# 2_waffling60-BK_matrix.net
KiCad netlist of a schematic drawn in Altium Designer
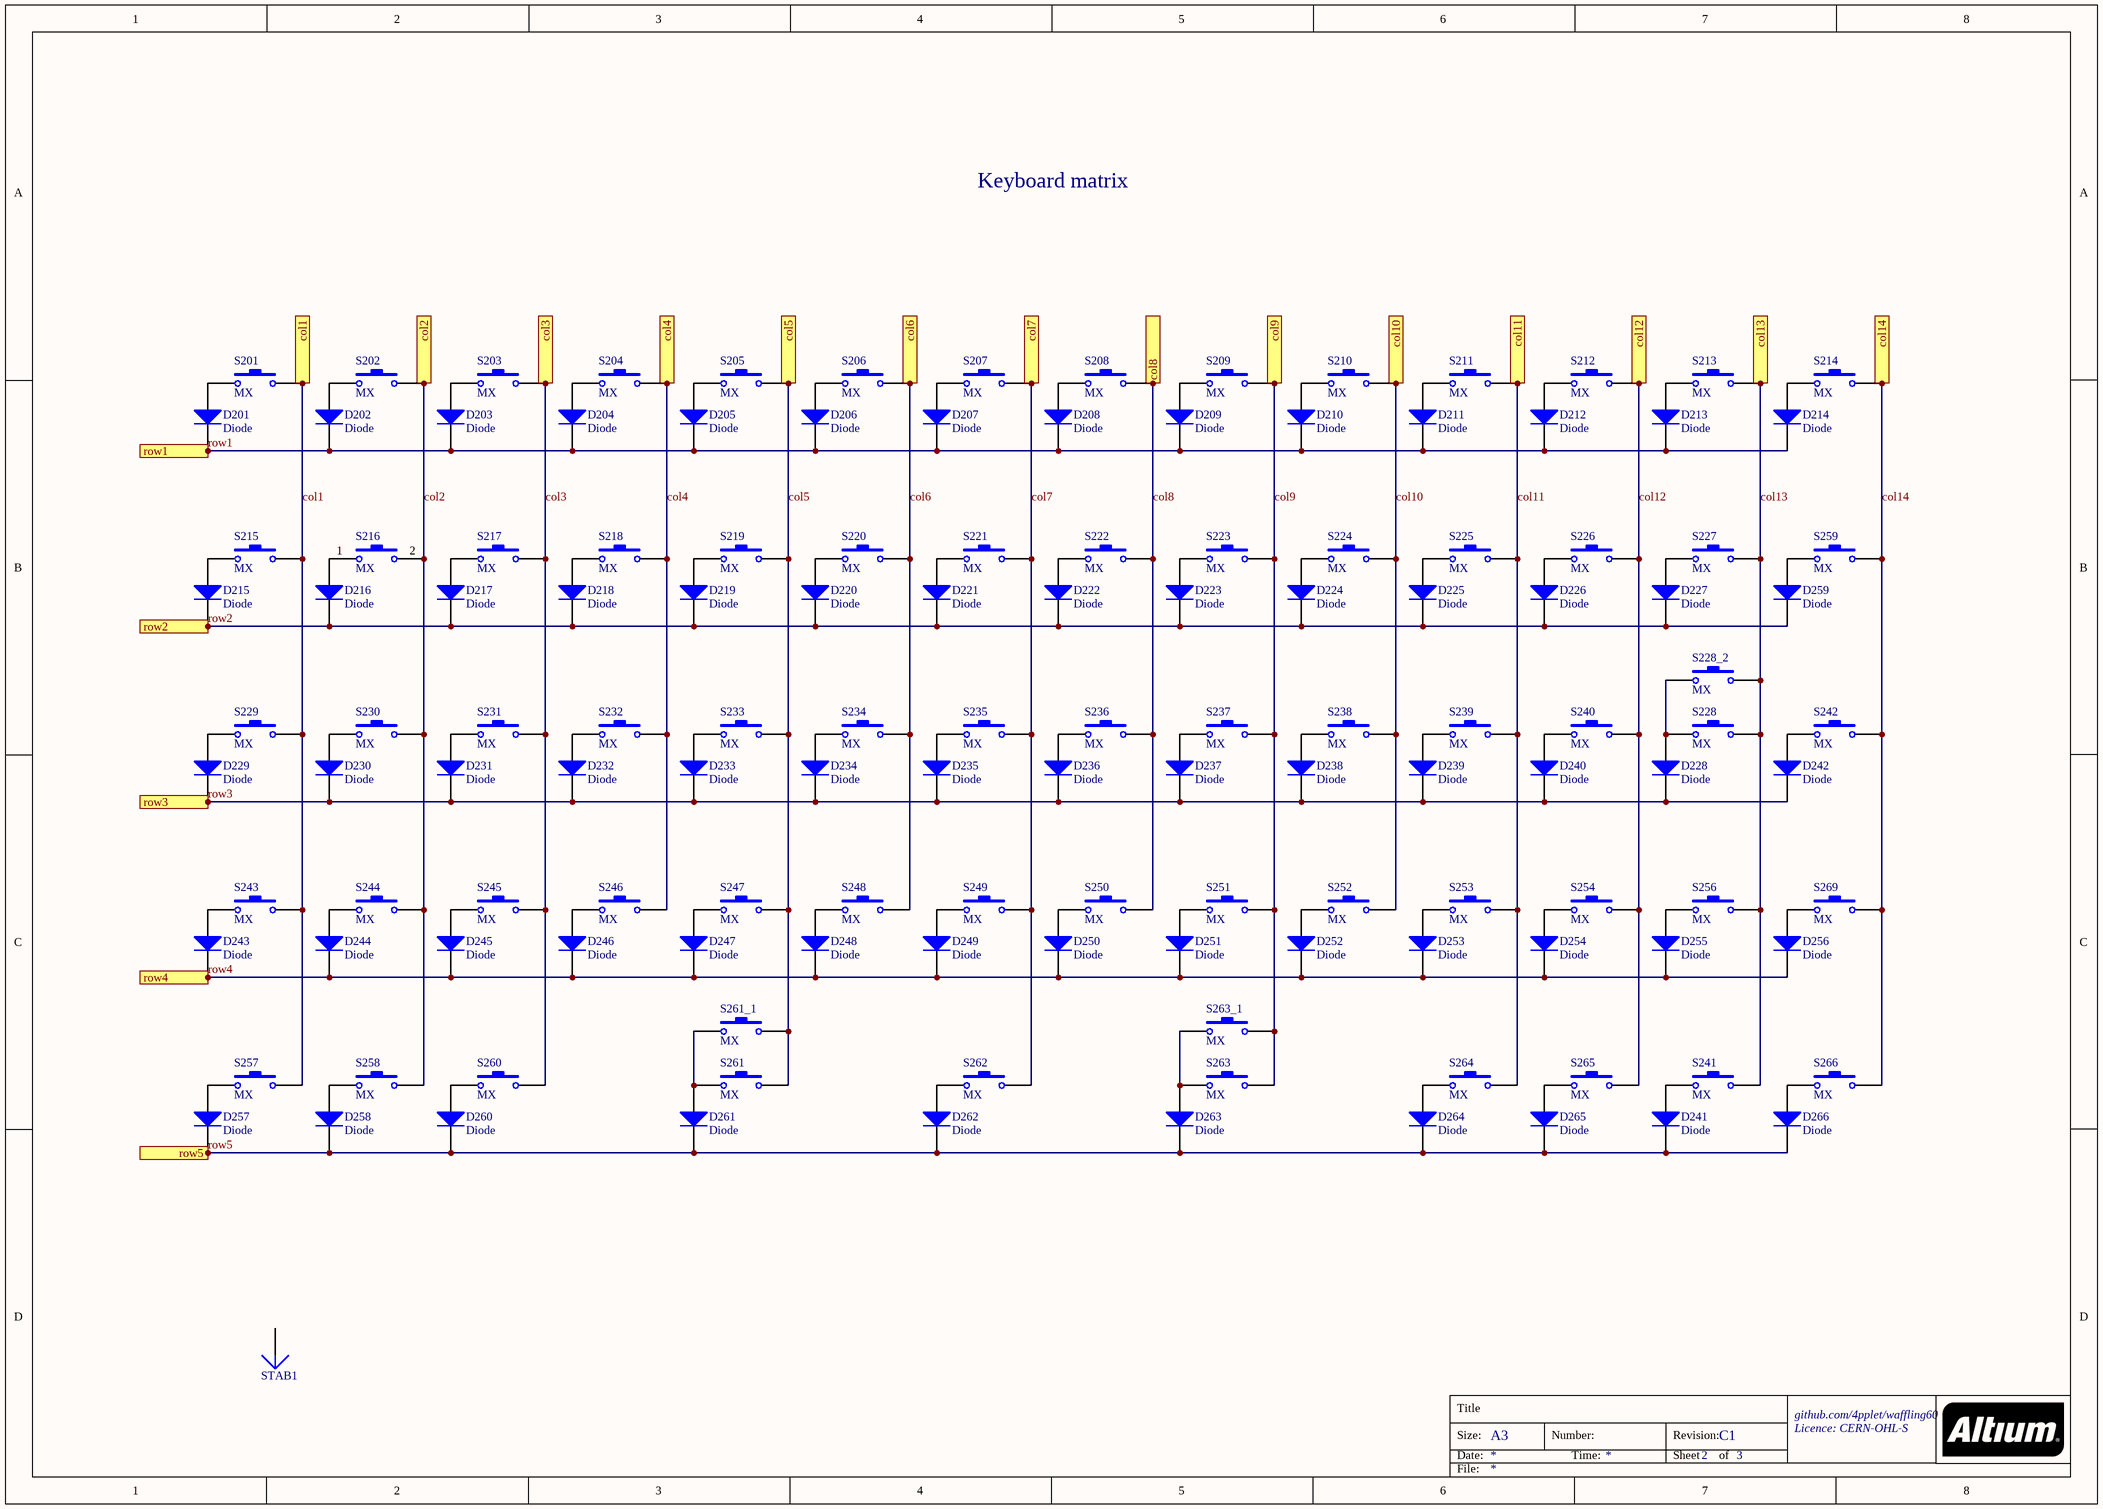
[diagram p0: 2_waffling60-BK_matrix.SchDoc]

(export (version "E")
  (design (tool "Eeschema 10.0.6"))
  (components
    (comp (ref "D201")
      (value "Diode")
      (footprint "SOD-123")
      (description "Default Diode")
      (fields (field (name "LCSC PART #") "C81598") (field (name "MRF.PART") "1N4148W"))
      (libsource (lib "Miscellaneous Devices") (part "Diode"))
    )
    (comp (ref "D202")
      (value "Diode")
      (footprint "SOD-123")
      (description "Default Diode")
      (fields (field (name "LCSC PART #") "C81598") (field (name "MRF.PART") "1N4148W"))
      (libsource (lib "Miscellaneous Devices") (part "Diode"))
    )
    (comp (ref "D203")
      (value "Diode")
      (footprint "SOD-123")
      (description "Default Diode")
      (fields (field (name "LCSC PART #") "C81598") (field (name "MRF.PART") "1N4148W"))
      (libsource (lib "Miscellaneous Devices") (part "Diode"))
    )
    (comp (ref "D204")
      (value "Diode")
      (footprint "SOD-123")
      (description "Default Diode")
      (fields (field (name "LCSC PART #") "C81598") (field (name "MRF.PART") "1N4148W"))
      (libsource (lib "Miscellaneous Devices") (part "Diode"))
    )
    (comp (ref "D205")
      (value "Diode")
      (footprint "SOD-123")
      (description "Default Diode")
      (fields (field (name "LCSC PART #") "C81598") (field (name "MRF.PART") "1N4148W"))
      (libsource (lib "Miscellaneous Devices") (part "Diode"))
    )
    (comp (ref "D206")
      (value "Diode")
      (footprint "SOD-123")
      (description "Default Diode")
      (fields (field (name "LCSC PART #") "C81598") (field (name "MRF.PART") "1N4148W"))
      (libsource (lib "Miscellaneous Devices") (part "Diode"))
    )
    (comp (ref "D207")
      (value "Diode")
      (footprint "SOD-123")
      (description "Default Diode")
      (fields (field (name "LCSC PART #") "C81598") (field (name "MRF.PART") "1N4148W"))
      (libsource (lib "Miscellaneous Devices") (part "Diode"))
    )
    (comp (ref "D208")
      (value "Diode")
      (footprint "SOD-123")
      (description "Default Diode")
      (fields (field (name "LCSC PART #") "C81598") (field (name "MRF.PART") "1N4148W"))
      (libsource (lib "Miscellaneous Devices") (part "Diode"))
    )
    (comp (ref "D209")
      (value "Diode")
      (footprint "SOD-123")
      (description "Default Diode")
      (fields (field (name "LCSC PART #") "C81598") (field (name "MRF.PART") "1N4148W"))
      (libsource (lib "Miscellaneous Devices") (part "Diode"))
    )
    (comp (ref "D210")
      (value "Diode")
      (footprint "SOD-123")
      (description "Default Diode")
      (fields (field (name "LCSC PART #") "C81598") (field (name "MRF.PART") "1N4148W"))
      (libsource (lib "Miscellaneous Devices") (part "Diode"))
    )
    (comp (ref "D211")
      (value "Diode")
      (footprint "SOD-123")
      (description "Default Diode")
      (fields (field (name "LCSC PART #") "C81598") (field (name "MRF.PART") "1N4148W"))
      (libsource (lib "Miscellaneous Devices") (part "Diode"))
    )
    (comp (ref "D212")
      (value "Diode")
      (footprint "SOD-123")
      (description "Default Diode")
      (fields (field (name "LCSC PART #") "C81598") (field (name "MRF.PART") "1N4148W"))
      (libsource (lib "Miscellaneous Devices") (part "Diode"))
    )
    (comp (ref "D213")
      (value "Diode")
      (footprint "SOD-123")
      (description "Default Diode")
      (fields (field (name "LCSC PART #") "C81598") (field (name "MRF.PART") "1N4148W"))
      (libsource (lib "Miscellaneous Devices") (part "Diode"))
    )
    (comp (ref "D214")
      (value "Diode")
      (footprint "SOD-123")
      (description "Default Diode")
      (fields (field (name "LCSC PART #") "C81598") (field (name "MRF.PART") "1N4148W"))
      (libsource (lib "Miscellaneous Devices") (part "Diode"))
    )
    (comp (ref "D215")
      (value "Diode")
      (footprint "SOD-123")
      (description "Default Diode")
      (fields (field (name "LCSC PART #") "C81598") (field (name "MRF.PART") "1N4148W"))
      (libsource (lib "Miscellaneous Devices") (part "Diode"))
    )
    (comp (ref "D216")
      (value "Diode")
      (footprint "SOD-123")
      (description "Default Diode")
      (fields (field (name "LCSC PART #") "C81598") (field (name "MRF.PART") "1N4148W"))
      (libsource (lib "Miscellaneous Devices") (part "Diode"))
    )
    (comp (ref "D217")
      (value "Diode")
      (footprint "SOD-123")
      (description "Default Diode")
      (fields (field (name "LCSC PART #") "C81598") (field (name "MRF.PART") "1N4148W"))
      (libsource (lib "Miscellaneous Devices") (part "Diode"))
    )
    (comp (ref "D218")
      (value "Diode")
      (footprint "SOD-123")
      (description "Default Diode")
      (fields (field (name "LCSC PART #") "C81598") (field (name "MRF.PART") "1N4148W"))
      (libsource (lib "Miscellaneous Devices") (part "Diode"))
    )
    (comp (ref "D219")
      (value "Diode")
      (footprint "SOD-123")
      (description "Default Diode")
      (fields (field (name "LCSC PART #") "C81598") (field (name "MRF.PART") "1N4148W"))
      (libsource (lib "Miscellaneous Devices") (part "Diode"))
    )
    (comp (ref "D220")
      (value "Diode")
      (footprint "SOD-123")
      (description "Default Diode")
      (fields (field (name "LCSC PART #") "C81598") (field (name "MRF.PART") "1N4148W"))
      (libsource (lib "Miscellaneous Devices") (part "Diode"))
    )
    (comp (ref "D221")
      (value "Diode")
      (footprint "SOD-123")
      (description "Default Diode")
      (fields (field (name "LCSC PART #") "C81598") (field (name "MRF.PART") "1N4148W"))
      (libsource (lib "Miscellaneous Devices") (part "Diode"))
    )
    (comp (ref "D222")
      (value "Diode")
      (footprint "SOD-123")
      (description "Default Diode")
      (fields (field (name "LCSC PART #") "C81598") (field (name "MRF.PART") "1N4148W"))
      (libsource (lib "Miscellaneous Devices") (part "Diode"))
    )
    (comp (ref "D223")
      (value "Diode")
      (footprint "SOD-123")
      (description "Default Diode")
      (fields (field (name "LCSC PART #") "C81598") (field (name "MRF.PART") "1N4148W"))
      (libsource (lib "Miscellaneous Devices") (part "Diode"))
    )
    (comp (ref "D224")
      (value "Diode")
      (footprint "SOD-123")
      (description "Default Diode")
      (fields (field (name "LCSC PART #") "C81598") (field (name "MRF.PART") "1N4148W"))
      (libsource (lib "Miscellaneous Devices") (part "Diode"))
    )
    (comp (ref "D225")
      (value "Diode")
      (footprint "SOD-123")
      (description "Default Diode")
      (fields (field (name "LCSC PART #") "C81598") (field (name "MRF.PART") "1N4148W"))
      (libsource (lib "Miscellaneous Devices") (part "Diode"))
    )
    (comp (ref "D226")
      (value "Diode")
      (footprint "SOD-123")
      (description "Default Diode")
      (fields (field (name "LCSC PART #") "C81598") (field (name "MRF.PART") "1N4148W"))
      (libsource (lib "Miscellaneous Devices") (part "Diode"))
    )
    (comp (ref "D227")
      (value "Diode")
      (footprint "SOD-123")
      (description "Default Diode")
      (fields (field (name "LCSC PART #") "C81598") (field (name "MRF.PART") "1N4148W"))
      (libsource (lib "Miscellaneous Devices") (part "Diode"))
    )
    (comp (ref "D228")
      (value "Diode")
      (footprint "SOD-123")
      (description "Default Diode")
      (fields (field (name "LCSC PART #") "C81598") (field (name "MRF.PART") "1N4148W"))
      (libsource (lib "Miscellaneous Devices") (part "Diode"))
    )
    (comp (ref "D229")
      (value "Diode")
      (footprint "SOD-123")
      (description "Default Diode")
      (fields (field (name "LCSC PART #") "C81598") (field (name "MRF.PART") "1N4148W"))
      (libsource (lib "Miscellaneous Devices") (part "Diode"))
    )
    (comp (ref "D230")
      (value "Diode")
      (footprint "SOD-123")
      (description "Default Diode")
      (fields (field (name "LCSC PART #") "C81598") (field (name "MRF.PART") "1N4148W"))
      (libsource (lib "Miscellaneous Devices") (part "Diode"))
    )
    (comp (ref "D231")
      (value "Diode")
      (footprint "SOD-123")
      (description "Default Diode")
      (fields (field (name "LCSC PART #") "C81598") (field (name "MRF.PART") "1N4148W"))
      (libsource (lib "Miscellaneous Devices") (part "Diode"))
    )
    (comp (ref "D232")
      (value "Diode")
      (footprint "SOD-123")
      (description "Default Diode")
      (fields (field (name "LCSC PART #") "C81598") (field (name "MRF.PART") "1N4148W"))
      (libsource (lib "Miscellaneous Devices") (part "Diode"))
    )
    (comp (ref "D233")
      (value "Diode")
      (footprint "SOD-123")
      (description "Default Diode")
      (fields (field (name "LCSC PART #") "C81598") (field (name "MRF.PART") "1N4148W"))
      (libsource (lib "Miscellaneous Devices") (part "Diode"))
    )
    (comp (ref "D234")
      (value "Diode")
      (footprint "SOD-123")
      (description "Default Diode")
      (fields (field (name "LCSC PART #") "C81598") (field (name "MRF.PART") "1N4148W"))
      (libsource (lib "Miscellaneous Devices") (part "Diode"))
    )
    (comp (ref "D235")
      (value "Diode")
      (footprint "SOD-123")
      (description "Default Diode")
      (fields (field (name "LCSC PART #") "C81598") (field (name "MRF.PART") "1N4148W"))
      (libsource (lib "Miscellaneous Devices") (part "Diode"))
    )
    (comp (ref "D236")
      (value "Diode")
      (footprint "SOD-123")
      (description "Default Diode")
      (fields (field (name "LCSC PART #") "C81598") (field (name "MRF.PART") "1N4148W"))
      (libsource (lib "Miscellaneous Devices") (part "Diode"))
    )
    (comp (ref "D237")
      (value "Diode")
      (footprint "SOD-123")
      (description "Default Diode")
      (fields (field (name "LCSC PART #") "C81598") (field (name "MRF.PART") "1N4148W"))
      (libsource (lib "Miscellaneous Devices") (part "Diode"))
    )
    (comp (ref "D238")
      (value "Diode")
      (footprint "SOD-123")
      (description "Default Diode")
      (fields (field (name "LCSC PART #") "C81598") (field (name "MRF.PART") "1N4148W"))
      (libsource (lib "Miscellaneous Devices") (part "Diode"))
    )
    (comp (ref "D239")
      (value "Diode")
      (footprint "SOD-123")
      (description "Default Diode")
      (fields (field (name "LCSC PART #") "C81598") (field (name "MRF.PART") "1N4148W"))
      (libsource (lib "Miscellaneous Devices") (part "Diode"))
    )
    (comp (ref "D240")
      (value "Diode")
      (footprint "SOD-123")
      (description "Default Diode")
      (fields (field (name "LCSC PART #") "C81598") (field (name "MRF.PART") "1N4148W"))
      (libsource (lib "Miscellaneous Devices") (part "Diode"))
    )
    (comp (ref "D241")
      (value "Diode")
      (footprint "SOD-123")
      (description "Default Diode")
      (fields (field (name "LCSC PART #") "C81598") (field (name "MRF.PART") "1N4148W"))
      (libsource (lib "Miscellaneous Devices") (part "Diode"))
    )
    (comp (ref "D242")
      (value "Diode")
      (footprint "SOD-123")
      (description "Default Diode")
      (fields (field (name "LCSC PART #") "C81598") (field (name "MRF.PART") "1N4148W"))
      (libsource (lib "Miscellaneous Devices") (part "Diode"))
    )
    (comp (ref "D243")
      (value "Diode")
      (footprint "SOD-123")
      (description "Default Diode")
      (fields (field (name "LCSC PART #") "C81598") (field (name "MRF.PART") "1N4148W"))
      (libsource (lib "Miscellaneous Devices") (part "Diode"))
    )
    (comp (ref "D244")
      (value "Diode")
      (footprint "SOD-123")
      (description "Default Diode")
      (fields (field (name "LCSC PART #") "C81598") (field (name "MRF.PART") "1N4148W"))
      (libsource (lib "Miscellaneous Devices") (part "Diode"))
    )
    (comp (ref "D245")
      (value "Diode")
      (footprint "SOD-123")
      (description "Default Diode")
      (fields (field (name "LCSC PART #") "C81598") (field (name "MRF.PART") "1N4148W"))
      (libsource (lib "Miscellaneous Devices") (part "Diode"))
    )
    (comp (ref "D246")
      (value "Diode")
      (footprint "SOD-123")
      (description "Default Diode")
      (fields (field (name "LCSC PART #") "C81598") (field (name "MRF.PART") "1N4148W"))
      (libsource (lib "Miscellaneous Devices") (part "Diode"))
    )
    (comp (ref "D247")
      (value "Diode")
      (footprint "SOD-123")
      (description "Default Diode")
      (fields (field (name "LCSC PART #") "C81598") (field (name "MRF.PART") "1N4148W"))
      (libsource (lib "Miscellaneous Devices") (part "Diode"))
    )
    (comp (ref "D248")
      (value "Diode")
      (footprint "SOD-123")
      (description "Default Diode")
      (fields (field (name "LCSC PART #") "C81598") (field (name "MRF.PART") "1N4148W"))
      (libsource (lib "Miscellaneous Devices") (part "Diode"))
    )
    (comp (ref "D249")
      (value "Diode")
      (footprint "SOD-123")
      (description "Default Diode")
      (fields (field (name "LCSC PART #") "C81598") (field (name "MRF.PART") "1N4148W"))
      (libsource (lib "Miscellaneous Devices") (part "Diode"))
    )
    (comp (ref "D250")
      (value "Diode")
      (footprint "SOD-123")
      (description "Default Diode")
      (fields (field (name "LCSC PART #") "C81598") (field (name "MRF.PART") "1N4148W"))
      (libsource (lib "Miscellaneous Devices") (part "Diode"))
    )
    (comp (ref "D251")
      (value "Diode")
      (footprint "SOD-123")
      (description "Default Diode")
      (fields (field (name "LCSC PART #") "C81598") (field (name "MRF.PART") "1N4148W"))
      (libsource (lib "Miscellaneous Devices") (part "Diode"))
    )
    (comp (ref "D252")
      (value "Diode")
      (footprint "SOD-123")
      (description "Default Diode")
      (fields (field (name "LCSC PART #") "C81598") (field (name "MRF.PART") "1N4148W"))
      (libsource (lib "Miscellaneous Devices") (part "Diode"))
    )
    (comp (ref "D253")
      (value "Diode")
      (footprint "SOD-123")
      (description "Default Diode")
      (fields (field (name "LCSC PART #") "C81598") (field (name "MRF.PART") "1N4148W"))
      (libsource (lib "Miscellaneous Devices") (part "Diode"))
    )
    (comp (ref "D254")
      (value "Diode")
      (footprint "SOD-123")
      (description "Default Diode")
      (fields (field (name "LCSC PART #") "C81598") (field (name "MRF.PART") "1N4148W"))
      (libsource (lib "Miscellaneous Devices") (part "Diode"))
    )
    (comp (ref "D255")
      (value "Diode")
      (footprint "SOD-123")
      (description "Default Diode")
      (fields (field (name "LCSC PART #") "C81598") (field (name "MRF.PART") "1N4148W"))
      (libsource (lib "Miscellaneous Devices") (part "Diode"))
    )
    (comp (ref "D256")
      (value "Diode")
      (footprint "SOD-123")
      (description "Default Diode")
      (fields (field (name "LCSC PART #") "C81598") (field (name "MRF.PART") "1N4148W"))
      (libsource (lib "Miscellaneous Devices") (part "Diode"))
    )
    (comp (ref "D257")
      (value "Diode")
      (footprint "SOD-123")
      (description "Default Diode")
      (fields (field (name "LCSC PART #") "C81598") (field (name "MRF.PART") "1N4148W"))
      (libsource (lib "Miscellaneous Devices") (part "Diode"))
    )
    (comp (ref "D258")
      (value "Diode")
      (footprint "SOD-123")
      (description "Default Diode")
      (fields (field (name "LCSC PART #") "C81598") (field (name "MRF.PART") "1N4148W"))
      (libsource (lib "Miscellaneous Devices") (part "Diode"))
    )
    (comp (ref "D259")
      (value "Diode")
      (footprint "SOD-123")
      (description "Default Diode")
      (fields (field (name "LCSC PART #") "C81598") (field (name "MRF.PART") "1N4148W"))
      (libsource (lib "Miscellaneous Devices") (part "Diode"))
    )
    (comp (ref "D260")
      (value "Diode")
      (footprint "SOD-123")
      (description "Default Diode")
      (fields (field (name "LCSC PART #") "C81598") (field (name "MRF.PART") "1N4148W"))
      (libsource (lib "Miscellaneous Devices") (part "Diode"))
    )
    (comp (ref "D261")
      (value "Diode")
      (footprint "SOD-123")
      (description "Default Diode")
      (fields (field (name "LCSC PART #") "C81598") (field (name "MRF.PART") "1N4148W"))
      (libsource (lib "Miscellaneous Devices") (part "Diode"))
    )
    (comp (ref "D262")
      (value "Diode")
      (footprint "SOD-123")
      (description "Default Diode")
      (fields (field (name "LCSC PART #") "C81598") (field (name "MRF.PART") "1N4148W"))
      (libsource (lib "Miscellaneous Devices") (part "Diode"))
    )
    (comp (ref "D263")
      (value "Diode")
      (footprint "SOD-123")
      (description "Default Diode")
      (fields (field (name "LCSC PART #") "C81598") (field (name "MRF.PART") "1N4148W"))
      (libsource (lib "Miscellaneous Devices") (part "Diode"))
    )
    (comp (ref "D264")
      (value "Diode")
      (footprint "SOD-123")
      (description "Default Diode")
      (fields (field (name "LCSC PART #") "C81598") (field (name "MRF.PART") "1N4148W"))
      (libsource (lib "Miscellaneous Devices") (part "Diode"))
    )
    (comp (ref "D265")
      (value "Diode")
      (footprint "SOD-123")
      (description "Default Diode")
      (fields (field (name "LCSC PART #") "C81598") (field (name "MRF.PART") "1N4148W"))
      (libsource (lib "Miscellaneous Devices") (part "Diode"))
    )
    (comp (ref "D266")
      (value "Diode")
      (footprint "SOD-123")
      (description "Default Diode")
      (fields (field (name "LCSC PART #") "C81598") (field (name "MRF.PART") "1N4148W"))
      (libsource (lib "Miscellaneous Devices") (part "Diode"))
    )
    (comp (ref "S201")
      (value "MX")
      (footprint "MX-switch - switched pol")
      (description "Switch")
      (libsource (lib "Miscellaneous Devices") (part "SW-PB"))
    )
    (comp (ref "S202")
      (value "MX")
      (footprint "MX-switch")
      (description "Switch")
      (libsource (lib "Miscellaneous Devices") (part "SW-PB"))
    )
    (comp (ref "S203")
      (value "MX")
      (footprint "MX-switch - switched pol")
      (description "Switch")
      (libsource (lib "Miscellaneous Devices") (part "SW-PB"))
    )
    (comp (ref "S204")
      (value "MX")
      (footprint "MX-switch - switched pol")
      (description "Switch")
      (libsource (lib "Miscellaneous Devices") (part "SW-PB"))
    )
    (comp (ref "S205")
      (value "MX")
      (footprint "MX-switch - switched pol")
      (description "Switch")
      (libsource (lib "Miscellaneous Devices") (part "SW-PB"))
    )
    (comp (ref "S206")
      (value "MX")
      (footprint "MX-switch - switched pol")
      (description "Switch")
      (libsource (lib "Miscellaneous Devices") (part "SW-PB"))
    )
    (comp (ref "S207")
      (value "MX")
      (footprint "MX-switch - switched pol")
      (description "Switch")
      (libsource (lib "Miscellaneous Devices") (part "SW-PB"))
    )
    (comp (ref "S208")
      (value "MX")
      (footprint "MX-switch - switched pol")
      (description "Switch")
      (libsource (lib "Miscellaneous Devices") (part "SW-PB"))
    )
    (comp (ref "S209")
      (value "MX")
      (footprint "MX-switch - switched pol")
      (description "Switch")
      (libsource (lib "Miscellaneous Devices") (part "SW-PB"))
    )
    (comp (ref "S210")
      (value "MX")
      (footprint "MX-switch - switched pol")
      (description "Switch")
      (libsource (lib "Miscellaneous Devices") (part "SW-PB"))
    )
    (comp (ref "S211")
      (value "MX")
      (footprint "MX-switch - switched pol")
      (description "Switch")
      (libsource (lib "Miscellaneous Devices") (part "SW-PB"))
    )
    (comp (ref "S212")
      (value "MX")
      (footprint "MX-switch - switched pol")
      (description "Switch")
      (libsource (lib "Miscellaneous Devices") (part "SW-PB"))
    )
    (comp (ref "S213")
      (value "MX")
      (footprint "MX-switch - switched pol")
      (description "Switch")
      (libsource (lib "Miscellaneous Devices") (part "SW-PB"))
    )
    (comp (ref "S214")
      (value "MX")
      (footprint "MX-switch")
      (description "Switch")
      (libsource (lib "Miscellaneous Devices") (part "SW-PB"))
    )
    (comp (ref "S215")
      (value "MX")
      (footprint "MX-switch - switched pol")
      (description "TAB")
      (libsource (lib "Miscellaneous Devices") (part "SW-PB"))
    )
    (comp (ref "S216")
      (value "MX")
      (footprint "MX-switch")
      (description "Switch")
      (libsource (lib "") (part "SW-PB_1"))
    )
    (comp (ref "S217")
      (value "MX")
      (footprint "MX-switch - switched pol")
      (description "Switch")
      (libsource (lib "Miscellaneous Devices") (part "SW-PB"))
    )
    (comp (ref "S218")
      (value "MX")
      (footprint "MX-switch - switched pol")
      (description "Switch")
      (libsource (lib "Miscellaneous Devices") (part "SW-PB"))
    )
    (comp (ref "S219")
      (value "MX")
      (footprint "MX-switch - switched pol")
      (description "Switch")
      (libsource (lib "Miscellaneous Devices") (part "SW-PB"))
    )
    (comp (ref "S220")
      (value "MX")
      (footprint "MX-switch")
      (description "Switch")
      (libsource (lib "Miscellaneous Devices") (part "SW-PB"))
    )
    (comp (ref "S221")
      (value "MX")
      (footprint "MX-switch - switched pol")
      (description "Switch")
      (libsource (lib "Miscellaneous Devices") (part "SW-PB"))
    )
    (comp (ref "S222")
      (value "MX")
      (footprint "MX-switch")
      (description "Switch")
      (libsource (lib "Miscellaneous Devices") (part "SW-PB"))
    )
    (comp (ref "S223")
      (value "MX")
      (footprint "MX-switch - switched pol")
      (description "Switch")
      (libsource (lib "Miscellaneous Devices") (part "SW-PB"))
    )
    (comp (ref "S224")
      (value "MX")
      (footprint "MX-switch - switched pol")
      (description "Switch")
      (libsource (lib "Miscellaneous Devices") (part "SW-PB"))
    )
    (comp (ref "S225")
      (value "MX")
      (footprint "MX-switch - switched pol")
      (description "Switch")
      (libsource (lib "Miscellaneous Devices") (part "SW-PB"))
    )
    (comp (ref "S226")
      (value "MX")
      (footprint "MX-switch")
      (description "Switch")
      (libsource (lib "Miscellaneous Devices") (part "SW-PB"))
    )
    (comp (ref "S227")
      (value "MX")
      (footprint "MX-switch")
      (description "Switch")
      (libsource (lib "Miscellaneous Devices") (part "SW-PB"))
    )
    (comp (ref "S228")
      (value "MX")
      (footprint "MX-switch - 1.5U - switched pol")
      (description "Switch")
      (libsource (lib "Miscellaneous Devices") (part "SW-PB"))
    )
    (comp (ref "S228_2")
      (value "MX")
      (footprint "MX-switch - switched pol")
      (description "Switch")
      (libsource (lib "Miscellaneous Devices") (part "SW-PB"))
    )
    (comp (ref "S229")
      (value "MX")
      (footprint "MX-switch - CAPS")
      (description "Switch")
      (libsource (lib "Miscellaneous Devices") (part "SW-PB"))
    )
    (comp (ref "S230")
      (value "MX")
      (footprint "MX-switch")
      (description "Switch")
      (libsource (lib "Miscellaneous Devices") (part "SW-PB"))
    )
    (comp (ref "S231")
      (value "MX")
      (footprint "MX-switch - switched pol")
      (description "Switch")
      (libsource (lib "Miscellaneous Devices") (part "SW-PB"))
    )
    (comp (ref "S232")
      (value "MX")
      (footprint "MX-switch - switched pol")
      (description "Switch")
      (libsource (lib "Miscellaneous Devices") (part "SW-PB"))
    )
    (comp (ref "S233")
      (value "MX")
      (footprint "MX-switch - switched pol")
      (description "Switch")
      (libsource (lib "Miscellaneous Devices") (part "SW-PB"))
    )
    (comp (ref "S234")
      (value "MX")
      (footprint "MX-switch - switched pol")
      (description "Switch")
      (libsource (lib "Miscellaneous Devices") (part "SW-PB"))
    )
    (comp (ref "S235")
      (value "MX")
      (footprint "MX-switch - switched pol")
      (description "Switch")
      (libsource (lib "Miscellaneous Devices") (part "SW-PB"))
    )
    (comp (ref "S236")
      (value "MX")
      (footprint "MX-switch - switched pol")
      (description "Switch")
      (libsource (lib "Miscellaneous Devices") (part "SW-PB"))
    )
    (comp (ref "S237")
      (value "MX")
      (footprint "MX-switch - switched pol")
      (description "Switch")
      (libsource (lib "Miscellaneous Devices") (part "SW-PB"))
    )
    (comp (ref "S238")
      (value "MX")
      (footprint "MX-switch - switched pol")
      (description "Switch")
      (libsource (lib "Miscellaneous Devices") (part "SW-PB"))
    )
    (comp (ref "S239")
      (value "MX")
      (footprint "MX-switch - switched pol")
      (description "Switch")
      (libsource (lib "Miscellaneous Devices") (part "SW-PB"))
    )
    (comp (ref "S240")
      (value "MX")
      (footprint "MX-switch - switched pol")
      (description "Switch")
      (libsource (lib "Miscellaneous Devices") (part "SW-PB"))
    )
    (comp (ref "S241")
      (value "MX")
      (footprint "MX-switch - 1u MOD-R")
      (description "Switch")
      (libsource (lib "Miscellaneous Devices") (part "SW-PB"))
    )
    (comp (ref "S242")
      (value "MX")
      (footprint "MX-switch - Enter - Rotated Stab")
      (description "Switch")
      (libsource (lib "Miscellaneous Devices") (part "SW-PB"))
    )
    (comp (ref "S243")
      (value "MX")
      (footprint "MX-switch - Left shift")
      (description "Switch")
      (libsource (lib "Miscellaneous Devices") (part "SW-PB"))
    )
    (comp (ref "S244")
      (value "MX")
      (footprint "MX-switch")
      (description "Switch")
      (libsource (lib "Miscellaneous Devices") (part "SW-PB"))
    )
    (comp (ref "S245")
      (value "MX")
      (footprint "MX-switch - switched pol")
      (description "Switch")
      (libsource (lib "Miscellaneous Devices") (part "SW-PB"))
    )
    (comp (ref "S246")
      (value "MX")
      (footprint "MX-switch - switched pol")
      (description "Switch")
      (libsource (lib "Miscellaneous Devices") (part "SW-PB"))
    )
    (comp (ref "S247")
      (value "MX")
      (footprint "MX-switch - switched pol")
      (description "Switch")
      (libsource (lib "Miscellaneous Devices") (part "SW-PB"))
    )
    (comp (ref "S248")
      (value "MX")
      (footprint "MX-switch - switched pol")
      (description "Switch")
      (libsource (lib "Miscellaneous Devices") (part "SW-PB"))
    )
    (comp (ref "S249")
      (value "MX")
      (footprint "MX-switch - switched pol")
      (description "Switch")
      (libsource (lib "Miscellaneous Devices") (part "SW-PB"))
    )
    (comp (ref "S250")
      (value "MX")
      (footprint "MX-switch - switched pol")
      (description "Switch")
      (libsource (lib "Miscellaneous Devices") (part "SW-PB"))
    )
    (comp (ref "S251")
      (value "MX")
      (footprint "MX-switch - switched pol")
      (description "Switch")
      (libsource (lib "Miscellaneous Devices") (part "SW-PB"))
    )
    (comp (ref "S252")
      (value "MX")
      (footprint "MX-switch - switched pol")
      (description "Switch")
      (libsource (lib "Miscellaneous Devices") (part "SW-PB"))
    )
    (comp (ref "S253")
      (value "MX")
      (footprint "MX-switch - switched pol")
      (description "Switch")
      (libsource (lib "Miscellaneous Devices") (part "SW-PB"))
    )
    (comp (ref "S254")
      (value "MX")
      (footprint "MX-switch - switched pol")
      (description "Switch")
      (libsource (lib "Miscellaneous Devices") (part "SW-PB"))
    )
    (comp (ref "S256")
      (value "MX")
      (footprint "MX-switch - right shift")
      (description "Switch")
      (libsource (lib "Miscellaneous Devices") (part "SW-PB"))
    )
    (comp (ref "S257")
      (value "MX")
      (footprint "MX-switch - 1.5u MOD-L")
      (description "Switch")
      (libsource (lib "Miscellaneous Devices") (part "SW-PB"))
    )
    (comp (ref "S258")
      (value "MX")
      (footprint "MX-switch - 1u MOD-L")
      (description "Switch")
      (libsource (lib "Miscellaneous Devices") (part "SW-PB"))
    )
    (comp (ref "S259")
      (value "MX")
      (footprint "MX-switch - backspace")
      (description "Switch")
      (libsource (lib "Miscellaneous Devices") (part "SW-PB"))
    )
    (comp (ref "S260")
      (value "MX")
      (footprint "MX-switch - 1.5u MOD-L")
      (description "Switch")
      (libsource (lib "Miscellaneous Devices") (part "SW-PB"))
    )
    (comp (ref "S261")
      (value "MX")
      (footprint "MX-SWITCH - L SPLIT SPACE_V2")
      (description "Switch")
      (libsource (lib "Miscellaneous Devices") (part "SW-PB"))
    )
    (comp (ref "S261_1")
      (value "MX")
      (footprint "MX-switch - 3U - rotated stab")
      (description "Switch")
      (libsource (lib "Miscellaneous Devices") (part "SW-PB"))
    )
    (comp (ref "S262")
      (value "MX")
      (footprint "MX-switch - Space_V3")
      (description "Switch")
      (libsource (lib "Miscellaneous Devices") (part "SW-PB"))
    )
    (comp (ref "S263")
      (value "MX")
      (footprint "MX-SWITCH - R SPLIT SPACE_V2")
      (description "Switch")
      (libsource (lib "Miscellaneous Devices") (part "SW-PB"))
    )
    (comp (ref "S263_1")
      (value "MX")
      (footprint "MX-switch - 3U - rotated stab")
      (description "Switch")
      (libsource (lib "Miscellaneous Devices") (part "SW-PB"))
    )
    (comp (ref "S264")
      (value "MX")
      (footprint "MX-switch - switched pol")
      (description "Switch")
      (libsource (lib "Miscellaneous Devices") (part "SW-PB"))
    )
    (comp (ref "S265")
      (value "MX")
      (footprint "MX-switch - 1.5u MOD-R")
      (description "Switch")
      (libsource (lib "Miscellaneous Devices") (part "SW-PB"))
    )
    (comp (ref "S266")
      (value "MX")
      (footprint "MX-switch - 1.5u MOD-R")
      (description "Switch")
      (libsource (lib "Miscellaneous Devices") (part "SW-PB"))
    )
    (comp (ref "S269")
      (value "MX")
      (footprint "MX-switch")
      (description "Switch")
      (libsource (lib "Miscellaneous Devices") (part "SW-PB"))
    )
    (comp (ref "STAB1")
      (value "Plug")
      (footprint "Stab 10U")
      (libsource (lib "Miscellaneous Connectors") (part "Plug"))
    )
  )
  (nets
    (net (code "1") (name "/col1") (class "Default")
      (node (ref "S201") (pin "2") (pinfunction "2_2") (pintype "passive"))
      (node (ref "S215") (pin "2") (pinfunction "2_2") (pintype "passive"))
      (node (ref "S229") (pin "1") (pinfunction "1_1") (pintype "passive"))
      (node (ref "S243") (pin "2") (pinfunction "2_2") (pintype "passive"))
      (node (ref "S257") (pin "1") (pinfunction "1_1") (pintype "passive"))
    )
    (net (code "2") (name "/col2") (class "Default")
      (node (ref "S202") (pin "2") (pinfunction "2_2") (pintype "passive"))
      (node (ref "S216") (pin "2") (pinfunction "2_2") (pintype "passive"))
      (node (ref "S230") (pin "2") (pinfunction "2_2") (pintype "passive"))
      (node (ref "S244") (pin "1") (pinfunction "1_1") (pintype "passive"))
      (node (ref "S258") (pin "2") (pinfunction "2_2") (pintype "passive"))
    )
    (net (code "3") (name "/col3") (class "Default")
      (node (ref "S203") (pin "2") (pinfunction "2_2") (pintype "passive"))
      (node (ref "S217") (pin "2") (pinfunction "2_2") (pintype "passive"))
      (node (ref "S231") (pin "2") (pinfunction "2_2") (pintype "passive"))
      (node (ref "S245") (pin "2") (pinfunction "2_2") (pintype "passive"))
      (node (ref "S260") (pin "2") (pinfunction "2_2") (pintype "passive"))
    )
    (net (code "4") (name "/col4") (class "Default")
      (node (ref "S204") (pin "2") (pinfunction "2_2") (pintype "passive"))
      (node (ref "S218") (pin "2") (pinfunction "2_2") (pintype "passive"))
      (node (ref "S232") (pin "2") (pinfunction "2_2") (pintype "passive"))
      (node (ref "S246") (pin "2") (pinfunction "2_2") (pintype "passive"))
    )
    (net (code "5") (name "/col5") (class "Default")
      (node (ref "S205") (pin "2") (pinfunction "2_2") (pintype "passive"))
      (node (ref "S219") (pin "2") (pinfunction "2_2") (pintype "passive"))
      (node (ref "S233") (pin "2") (pinfunction "2_2") (pintype "passive"))
      (node (ref "S247") (pin "2") (pinfunction "2_2") (pintype "passive"))
      (node (ref "S261") (pin "2") (pinfunction "2_2") (pintype "passive"))
      (node (ref "S261_1") (pin "2") (pinfunction "2_2") (pintype "passive"))
    )
    (net (code "6") (name "/col6") (class "Default")
      (node (ref "S206") (pin "2") (pinfunction "2_2") (pintype "passive"))
      (node (ref "S220") (pin "2") (pinfunction "2_2") (pintype "passive"))
      (node (ref "S234") (pin "2") (pinfunction "2_2") (pintype "passive"))
      (node (ref "S248") (pin "2") (pinfunction "2_2") (pintype "passive"))
    )
    (net (code "7") (name "/col7") (class "Default")
      (node (ref "S207") (pin "2") (pinfunction "2_2") (pintype "passive"))
      (node (ref "S221") (pin "2") (pinfunction "2_2") (pintype "passive"))
      (node (ref "S235") (pin "2") (pinfunction "2_2") (pintype "passive"))
      (node (ref "S249") (pin "2") (pinfunction "2_2") (pintype "passive"))
      (node (ref "S262") (pin "1") (pinfunction "1_1") (pintype "passive"))
    )
    (net (code "8") (name "/col8") (class "Default")
      (node (ref "S208") (pin "2") (pinfunction "2_2") (pintype "passive"))
      (node (ref "S222") (pin "2") (pinfunction "2_2") (pintype "passive"))
      (node (ref "S236") (pin "2") (pinfunction "2_2") (pintype "passive"))
      (node (ref "S250") (pin "2") (pinfunction "2_2") (pintype "passive"))
    )
    (net (code "9") (name "/col9") (class "Default")
      (node (ref "S209") (pin "2") (pinfunction "2_2") (pintype "passive"))
      (node (ref "S223") (pin "2") (pinfunction "2_2") (pintype "passive"))
      (node (ref "S237") (pin "2") (pinfunction "2_2") (pintype "passive"))
      (node (ref "S251") (pin "2") (pinfunction "2_2") (pintype "passive"))
      (node (ref "S263") (pin "1") (pinfunction "1_1") (pintype "passive"))
      (node (ref "S263_1") (pin "1") (pinfunction "1_1") (pintype "passive"))
    )
    (net (code "10") (name "/col10") (class "Default")
      (node (ref "S210") (pin "2") (pinfunction "2_2") (pintype "passive"))
      (node (ref "S224") (pin "2") (pinfunction "2_2") (pintype "passive"))
      (node (ref "S238") (pin "2") (pinfunction "2_2") (pintype "passive"))
      (node (ref "S252") (pin "2") (pinfunction "2_2") (pintype "passive"))
    )
    (net (code "11") (name "/col11") (class "Default")
      (node (ref "S211") (pin "2") (pinfunction "2_2") (pintype "passive"))
      (node (ref "S225") (pin "2") (pinfunction "2_2") (pintype "passive"))
      (node (ref "S239") (pin "2") (pinfunction "2_2") (pintype "passive"))
      (node (ref "S253") (pin "2") (pinfunction "2_2") (pintype "passive"))
      (node (ref "S264") (pin "2") (pinfunction "2_2") (pintype "passive"))
    )
    (net (code "12") (name "/col12") (class "Default")
      (node (ref "S212") (pin "2") (pinfunction "2_2") (pintype "passive"))
      (node (ref "S226") (pin "2") (pinfunction "2_2") (pintype "passive"))
      (node (ref "S240") (pin "2") (pinfunction "2_2") (pintype "passive"))
      (node (ref "S254") (pin "2") (pinfunction "2_2") (pintype "passive"))
      (node (ref "S265") (pin "1") (pinfunction "1_1") (pintype "passive"))
    )
    (net (code "13") (name "/col13") (class "Default")
      (node (ref "S213") (pin "2") (pinfunction "2_2") (pintype "passive"))
      (node (ref "S227") (pin "2") (pinfunction "2_2") (pintype "passive"))
      (node (ref "S228") (pin "2") (pinfunction "2_2") (pintype "passive"))
      (node (ref "S228_2") (pin "2") (pinfunction "2_2") (pintype "passive"))
      (node (ref "S241") (pin "1") (pinfunction "1_1") (pintype "passive"))
      (node (ref "S256") (pin "2") (pinfunction "2_2") (pintype "passive"))
    )
    (net (code "14") (name "/col14") (class "Default")
      (node (ref "S214") (pin "2") (pinfunction "2_2") (pintype "passive"))
      (node (ref "S242") (pin "2") (pinfunction "2_2") (pintype "passive"))
      (node (ref "S259") (pin "2") (pinfunction "2_2") (pintype "passive"))
      (node (ref "S266") (pin "2") (pinfunction "2_2") (pintype "passive"))
      (node (ref "S269") (pin "2") (pinfunction "2_2") (pintype "passive"))
    )
    (net (code "15") (name "/row1") (class "Default")
      (node (ref "D201") (pin "2") (pinfunction "K_2") (pintype "passive"))
      (node (ref "D202") (pin "2") (pinfunction "K_2") (pintype "passive"))
      (node (ref "D203") (pin "2") (pinfunction "K_2") (pintype "passive"))
      (node (ref "D204") (pin "2") (pinfunction "K_2") (pintype "passive"))
      (node (ref "D205") (pin "2") (pinfunction "K_2") (pintype "passive"))
      (node (ref "D206") (pin "2") (pinfunction "K_2") (pintype "passive"))
      (node (ref "D207") (pin "2") (pinfunction "K_2") (pintype "passive"))
      (node (ref "D208") (pin "2") (pinfunction "K_2") (pintype "passive"))
      (node (ref "D209") (pin "2") (pinfunction "K_2") (pintype "passive"))
      (node (ref "D210") (pin "2") (pinfunction "K_2") (pintype "passive"))
      (node (ref "D211") (pin "2") (pinfunction "K_2") (pintype "passive"))
      (node (ref "D212") (pin "2") (pinfunction "K_2") (pintype "passive"))
      (node (ref "D213") (pin "2") (pinfunction "K_2") (pintype "passive"))
      (node (ref "D214") (pin "2") (pinfunction "K_2") (pintype "passive"))
    )
    (net (code "16") (name "/row2") (class "Default")
      (node (ref "D215") (pin "2") (pinfunction "K_2") (pintype "passive"))
      (node (ref "D216") (pin "2") (pinfunction "K_2") (pintype "passive"))
      (node (ref "D217") (pin "2") (pinfunction "K_2") (pintype "passive"))
      (node (ref "D218") (pin "2") (pinfunction "K_2") (pintype "passive"))
      (node (ref "D219") (pin "2") (pinfunction "K_2") (pintype "passive"))
      (node (ref "D220") (pin "2") (pinfunction "K_2") (pintype "passive"))
      (node (ref "D221") (pin "2") (pinfunction "K_2") (pintype "passive"))
      (node (ref "D222") (pin "2") (pinfunction "K_2") (pintype "passive"))
      (node (ref "D223") (pin "2") (pinfunction "K_2") (pintype "passive"))
      (node (ref "D224") (pin "2") (pinfunction "K_2") (pintype "passive"))
      (node (ref "D225") (pin "2") (pinfunction "K_2") (pintype "passive"))
      (node (ref "D226") (pin "2") (pinfunction "K_2") (pintype "passive"))
      (node (ref "D227") (pin "2") (pinfunction "K_2") (pintype "passive"))
      (node (ref "D259") (pin "2") (pinfunction "K_2") (pintype "passive"))
    )
    (net (code "17") (name "/row3") (class "Default")
      (node (ref "D228") (pin "2") (pinfunction "K_2") (pintype "passive"))
      (node (ref "D229") (pin "2") (pinfunction "K_2") (pintype "passive"))
      (node (ref "D230") (pin "2") (pinfunction "K_2") (pintype "passive"))
      (node (ref "D231") (pin "2") (pinfunction "K_2") (pintype "passive"))
      (node (ref "D232") (pin "2") (pinfunction "K_2") (pintype "passive"))
      (node (ref "D233") (pin "2") (pinfunction "K_2") (pintype "passive"))
      (node (ref "D234") (pin "2") (pinfunction "K_2") (pintype "passive"))
      (node (ref "D235") (pin "2") (pinfunction "K_2") (pintype "passive"))
      (node (ref "D236") (pin "2") (pinfunction "K_2") (pintype "passive"))
      (node (ref "D237") (pin "2") (pinfunction "K_2") (pintype "passive"))
      (node (ref "D238") (pin "2") (pinfunction "K_2") (pintype "passive"))
      (node (ref "D239") (pin "2") (pinfunction "K_2") (pintype "passive"))
      (node (ref "D240") (pin "2") (pinfunction "K_2") (pintype "passive"))
      (node (ref "D242") (pin "2") (pinfunction "K_2") (pintype "passive"))
    )
    (net (code "18") (name "/row4") (class "Default")
      (node (ref "D243") (pin "2") (pinfunction "K_2") (pintype "passive"))
      (node (ref "D244") (pin "2") (pinfunction "K_2") (pintype "passive"))
      (node (ref "D245") (pin "2") (pinfunction "K_2") (pintype "passive"))
      (node (ref "D246") (pin "2") (pinfunction "K_2") (pintype "passive"))
      (node (ref "D247") (pin "2") (pinfunction "K_2") (pintype "passive"))
      (node (ref "D248") (pin "2") (pinfunction "K_2") (pintype "passive"))
      (node (ref "D249") (pin "2") (pinfunction "K_2") (pintype "passive"))
      (node (ref "D250") (pin "2") (pinfunction "K_2") (pintype "passive"))
      (node (ref "D251") (pin "2") (pinfunction "K_2") (pintype "passive"))
      (node (ref "D252") (pin "2") (pinfunction "K_2") (pintype "passive"))
      (node (ref "D253") (pin "2") (pinfunction "K_2") (pintype "passive"))
      (node (ref "D254") (pin "2") (pinfunction "K_2") (pintype "passive"))
      (node (ref "D255") (pin "2") (pinfunction "K_2") (pintype "passive"))
      (node (ref "D256") (pin "2") (pinfunction "K_2") (pintype "passive"))
    )
    (net (code "19") (name "/row5") (class "Default")
      (node (ref "D241") (pin "2") (pinfunction "K_2") (pintype "passive"))
      (node (ref "D257") (pin "2") (pinfunction "K_2") (pintype "passive"))
      (node (ref "D258") (pin "2") (pinfunction "K_2") (pintype "passive"))
      (node (ref "D260") (pin "2") (pinfunction "K_2") (pintype "passive"))
      (node (ref "D261") (pin "2") (pinfunction "K_2") (pintype "passive"))
      (node (ref "D262") (pin "2") (pinfunction "K_2") (pintype "passive"))
      (node (ref "D263") (pin "2") (pinfunction "K_2") (pintype "passive"))
      (node (ref "D264") (pin "2") (pinfunction "K_2") (pintype "passive"))
      (node (ref "D265") (pin "2") (pinfunction "K_2") (pintype "passive"))
      (node (ref "D266") (pin "2") (pinfunction "K_2") (pintype "passive"))
    )
    (net (code "20") (name "Net-(D201-A)") (class "Default")
      (node (ref "D201") (pin "1") (pinfunction "A_1") (pintype "passive"))
      (node (ref "S201") (pin "1") (pinfunction "1_1") (pintype "passive"))
    )
    (net (code "21") (name "Net-(D202-A)") (class "Default")
      (node (ref "D202") (pin "1") (pinfunction "A_1") (pintype "passive"))
      (node (ref "S202") (pin "1") (pinfunction "1_1") (pintype "passive"))
    )
    (net (code "22") (name "Net-(D203-A)") (class "Default")
      (node (ref "D203") (pin "1") (pinfunction "A_1") (pintype "passive"))
      (node (ref "S203") (pin "1") (pinfunction "1_1") (pintype "passive"))
    )
    (net (code "23") (name "Net-(D204-A)") (class "Default")
      (node (ref "D204") (pin "1") (pinfunction "A_1") (pintype "passive"))
      (node (ref "S204") (pin "1") (pinfunction "1_1") (pintype "passive"))
    )
    (net (code "24") (name "Net-(D205-A)") (class "Default")
      (node (ref "D205") (pin "1") (pinfunction "A_1") (pintype "passive"))
      (node (ref "S205") (pin "1") (pinfunction "1_1") (pintype "passive"))
    )
    (net (code "25") (name "Net-(D206-A)") (class "Default")
      (node (ref "D206") (pin "1") (pinfunction "A_1") (pintype "passive"))
      (node (ref "S206") (pin "1") (pinfunction "1_1") (pintype "passive"))
    )
    (net (code "26") (name "Net-(D207-A)") (class "Default")
      (node (ref "D207") (pin "1") (pinfunction "A_1") (pintype "passive"))
      (node (ref "S207") (pin "1") (pinfunction "1_1") (pintype "passive"))
    )
    (net (code "27") (name "Net-(D208-A)") (class "Default")
      (node (ref "D208") (pin "1") (pinfunction "A_1") (pintype "passive"))
      (node (ref "S208") (pin "1") (pinfunction "1_1") (pintype "passive"))
    )
    (net (code "28") (name "Net-(D209-A)") (class "Default")
      (node (ref "D209") (pin "1") (pinfunction "A_1") (pintype "passive"))
      (node (ref "S209") (pin "1") (pinfunction "1_1") (pintype "passive"))
    )
    (net (code "29") (name "Net-(D210-A)") (class "Default")
      (node (ref "D210") (pin "1") (pinfunction "A_1") (pintype "passive"))
      (node (ref "S210") (pin "1") (pinfunction "1_1") (pintype "passive"))
    )
    (net (code "30") (name "Net-(D211-A)") (class "Default")
      (node (ref "D211") (pin "1") (pinfunction "A_1") (pintype "passive"))
      (node (ref "S211") (pin "1") (pinfunction "1_1") (pintype "passive"))
    )
    (net (code "31") (name "Net-(D212-A)") (class "Default")
      (node (ref "D212") (pin "1") (pinfunction "A_1") (pintype "passive"))
      (node (ref "S212") (pin "1") (pinfunction "1_1") (pintype "passive"))
    )
    (net (code "32") (name "Net-(D213-A)") (class "Default")
      (node (ref "D213") (pin "1") (pinfunction "A_1") (pintype "passive"))
      (node (ref "S213") (pin "1") (pinfunction "1_1") (pintype "passive"))
    )
    (net (code "33") (name "Net-(D214-A)") (class "Default")
      (node (ref "D214") (pin "1") (pinfunction "A_1") (pintype "passive"))
      (node (ref "S214") (pin "1") (pinfunction "1_1") (pintype "passive"))
    )
    (net (code "34") (name "Net-(D215-A)") (class "Default")
      (node (ref "D215") (pin "1") (pinfunction "A_1") (pintype "passive"))
      (node (ref "S215") (pin "1") (pinfunction "1_1") (pintype "passive"))
    )
    (net (code "35") (name "Net-(D216-A)") (class "Default")
      (node (ref "D216") (pin "1") (pinfunction "A_1") (pintype "passive"))
      (node (ref "S216") (pin "1") (pinfunction "1_1") (pintype "passive"))
    )
    (net (code "36") (name "Net-(D217-A)") (class "Default")
      (node (ref "D217") (pin "1") (pinfunction "A_1") (pintype "passive"))
      (node (ref "S217") (pin "1") (pinfunction "1_1") (pintype "passive"))
    )
    (net (code "37") (name "Net-(D218-A)") (class "Default")
      (node (ref "D218") (pin "1") (pinfunction "A_1") (pintype "passive"))
      (node (ref "S218") (pin "1") (pinfunction "1_1") (pintype "passive"))
    )
    (net (code "38") (name "Net-(D219-A)") (class "Default")
      (node (ref "D219") (pin "1") (pinfunction "A_1") (pintype "passive"))
      (node (ref "S219") (pin "1") (pinfunction "1_1") (pintype "passive"))
    )
    (net (code "39") (name "Net-(D220-A)") (class "Default")
      (node (ref "D220") (pin "1") (pinfunction "A_1") (pintype "passive"))
      (node (ref "S220") (pin "1") (pinfunction "1_1") (pintype "passive"))
    )
    (net (code "40") (name "Net-(D221-A)") (class "Default")
      (node (ref "D221") (pin "1") (pinfunction "A_1") (pintype "passive"))
      (node (ref "S221") (pin "1") (pinfunction "1_1") (pintype "passive"))
    )
    (net (code "41") (name "Net-(D222-A)") (class "Default")
      (node (ref "D222") (pin "1") (pinfunction "A_1") (pintype "passive"))
      (node (ref "S222") (pin "1") (pinfunction "1_1") (pintype "passive"))
    )
    (net (code "42") (name "Net-(D223-A)") (class "Default")
      (node (ref "D223") (pin "1") (pinfunction "A_1") (pintype "passive"))
      (node (ref "S223") (pin "1") (pinfunction "1_1") (pintype "passive"))
    )
    (net (code "43") (name "Net-(D224-A)") (class "Default")
      (node (ref "D224") (pin "1") (pinfunction "A_1") (pintype "passive"))
      (node (ref "S224") (pin "1") (pinfunction "1_1") (pintype "passive"))
    )
    (net (code "44") (name "Net-(D225-A)") (class "Default")
      (node (ref "D225") (pin "1") (pinfunction "A_1") (pintype "passive"))
      (node (ref "S225") (pin "1") (pinfunction "1_1") (pintype "passive"))
    )
    (net (code "45") (name "Net-(D226-A)") (class "Default")
      (node (ref "D226") (pin "1") (pinfunction "A_1") (pintype "passive"))
      (node (ref "S226") (pin "1") (pinfunction "1_1") (pintype "passive"))
    )
    (net (code "46") (name "Net-(D227-A)") (class "Default")
      (node (ref "D227") (pin "1") (pinfunction "A_1") (pintype "passive"))
      (node (ref "S227") (pin "1") (pinfunction "1_1") (pintype "passive"))
    )
    (net (code "47") (name "Net-(D228-A)") (class "Default")
      (node (ref "D228") (pin "1") (pinfunction "A_1") (pintype "passive"))
      (node (ref "S228") (pin "1") (pinfunction "1_1") (pintype "passive"))
      (node (ref "S228_2") (pin "1") (pinfunction "1_1") (pintype "passive"))
    )
    (net (code "48") (name "Net-(D229-A)") (class "Default")
      (node (ref "D229") (pin "1") (pinfunction "A_1") (pintype "passive"))
      (node (ref "S229") (pin "2") (pinfunction "2_2") (pintype "passive"))
    )
    (net (code "49") (name "Net-(D230-A)") (class "Default")
      (node (ref "D230") (pin "1") (pinfunction "A_1") (pintype "passive"))
      (node (ref "S230") (pin "1") (pinfunction "1_1") (pintype "passive"))
    )
    (net (code "50") (name "Net-(D231-A)") (class "Default")
      (node (ref "D231") (pin "1") (pinfunction "A_1") (pintype "passive"))
      (node (ref "S231") (pin "1") (pinfunction "1_1") (pintype "passive"))
    )
    (net (code "51") (name "Net-(D232-A)") (class "Default")
      (node (ref "D232") (pin "1") (pinfunction "A_1") (pintype "passive"))
      (node (ref "S232") (pin "1") (pinfunction "1_1") (pintype "passive"))
    )
    (net (code "52") (name "Net-(D233-A)") (class "Default")
      (node (ref "D233") (pin "1") (pinfunction "A_1") (pintype "passive"))
      (node (ref "S233") (pin "1") (pinfunction "1_1") (pintype "passive"))
    )
    (net (code "53") (name "Net-(D234-A)") (class "Default")
      (node (ref "D234") (pin "1") (pinfunction "A_1") (pintype "passive"))
      (node (ref "S234") (pin "1") (pinfunction "1_1") (pintype "passive"))
    )
    (net (code "54") (name "Net-(D235-A)") (class "Default")
      (node (ref "D235") (pin "1") (pinfunction "A_1") (pintype "passive"))
      (node (ref "S235") (pin "1") (pinfunction "1_1") (pintype "passive"))
    )
    (net (code "55") (name "Net-(D236-A)") (class "Default")
      (node (ref "D236") (pin "1") (pinfunction "A_1") (pintype "passive"))
      (node (ref "S236") (pin "1") (pinfunction "1_1") (pintype "passive"))
    )
    (net (code "56") (name "Net-(D237-A)") (class "Default")
      (node (ref "D237") (pin "1") (pinfunction "A_1") (pintype "passive"))
      (node (ref "S237") (pin "1") (pinfunction "1_1") (pintype "passive"))
    )
    (net (code "57") (name "Net-(D238-A)") (class "Default")
      (node (ref "D238") (pin "1") (pinfunction "A_1") (pintype "passive"))
      (node (ref "S238") (pin "1") (pinfunction "1_1") (pintype "passive"))
    )
    (net (code "58") (name "Net-(D239-A)") (class "Default")
      (node (ref "D239") (pin "1") (pinfunction "A_1") (pintype "passive"))
      (node (ref "S239") (pin "1") (pinfunction "1_1") (pintype "passive"))
    )
    (net (code "59") (name "Net-(D240-A)") (class "Default")
      (node (ref "D240") (pin "1") (pinfunction "A_1") (pintype "passive"))
      (node (ref "S240") (pin "1") (pinfunction "1_1") (pintype "passive"))
    )
    (net (code "60") (name "Net-(D241-A)") (class "Default")
      (node (ref "D241") (pin "1") (pinfunction "A_1") (pintype "passive"))
      (node (ref "S241") (pin "2") (pinfunction "2_2") (pintype "passive"))
    )
    (net (code "61") (name "Net-(D242-A)") (class "Default")
      (node (ref "D242") (pin "1") (pinfunction "A_1") (pintype "passive"))
      (node (ref "S242") (pin "1") (pinfunction "1_1") (pintype "passive"))
    )
    (net (code "62") (name "Net-(D243-A)") (class "Default")
      (node (ref "D243") (pin "1") (pinfunction "A_1") (pintype "passive"))
      (node (ref "S243") (pin "1") (pinfunction "1_1") (pintype "passive"))
    )
    (net (code "63") (name "Net-(D244-A)") (class "Default")
      (node (ref "D244") (pin "1") (pinfunction "A_1") (pintype "passive"))
      (node (ref "S244") (pin "2") (pinfunction "2_2") (pintype "passive"))
    )
    (net (code "64") (name "Net-(D245-A)") (class "Default")
      (node (ref "D245") (pin "1") (pinfunction "A_1") (pintype "passive"))
      (node (ref "S245") (pin "1") (pinfunction "1_1") (pintype "passive"))
    )
    (net (code "65") (name "Net-(D246-A)") (class "Default")
      (node (ref "D246") (pin "1") (pinfunction "A_1") (pintype "passive"))
      (node (ref "S246") (pin "1") (pinfunction "1_1") (pintype "passive"))
    )
    (net (code "66") (name "Net-(D247-A)") (class "Default")
      (node (ref "D247") (pin "1") (pinfunction "A_1") (pintype "passive"))
      (node (ref "S247") (pin "1") (pinfunction "1_1") (pintype "passive"))
    )
    (net (code "67") (name "Net-(D248-A)") (class "Default")
      (node (ref "D248") (pin "1") (pinfunction "A_1") (pintype "passive"))
      (node (ref "S248") (pin "1") (pinfunction "1_1") (pintype "passive"))
    )
    (net (code "68") (name "Net-(D249-A)") (class "Default")
      (node (ref "D249") (pin "1") (pinfunction "A_1") (pintype "passive"))
      (node (ref "S249") (pin "1") (pinfunction "1_1") (pintype "passive"))
    )
    (net (code "69") (name "Net-(D250-A)") (class "Default")
      (node (ref "D250") (pin "1") (pinfunction "A_1") (pintype "passive"))
      (node (ref "S250") (pin "1") (pinfunction "1_1") (pintype "passive"))
    )
    (net (code "70") (name "Net-(D251-A)") (class "Default")
      (node (ref "D251") (pin "1") (pinfunction "A_1") (pintype "passive"))
      (node (ref "S251") (pin "1") (pinfunction "1_1") (pintype "passive"))
    )
    (net (code "71") (name "Net-(D252-A)") (class "Default")
      (node (ref "D252") (pin "1") (pinfunction "A_1") (pintype "passive"))
      (node (ref "S252") (pin "1") (pinfunction "1_1") (pintype "passive"))
    )
    (net (code "72") (name "Net-(D253-A)") (class "Default")
      (node (ref "D253") (pin "1") (pinfunction "A_1") (pintype "passive"))
      (node (ref "S253") (pin "1") (pinfunction "1_1") (pintype "passive"))
    )
    (net (code "73") (name "Net-(D254-A)") (class "Default")
      (node (ref "D254") (pin "1") (pinfunction "A_1") (pintype "passive"))
      (node (ref "S254") (pin "1") (pinfunction "1_1") (pintype "passive"))
    )
    (net (code "74") (name "Net-(D255-A)") (class "Default")
      (node (ref "D255") (pin "1") (pinfunction "A_1") (pintype "passive"))
      (node (ref "S256") (pin "1") (pinfunction "1_1") (pintype "passive"))
    )
    (net (code "75") (name "Net-(D256-A)") (class "Default")
      (node (ref "D256") (pin "1") (pinfunction "A_1") (pintype "passive"))
      (node (ref "S269") (pin "1") (pinfunction "1_1") (pintype "passive"))
    )
    (net (code "76") (name "Net-(D257-A)") (class "Default")
      (node (ref "D257") (pin "1") (pinfunction "A_1") (pintype "passive"))
      (node (ref "S257") (pin "2") (pinfunction "2_2") (pintype "passive"))
    )
    (net (code "77") (name "Net-(D258-A)") (class "Default")
      (node (ref "D258") (pin "1") (pinfunction "A_1") (pintype "passive"))
      (node (ref "S258") (pin "1") (pinfunction "1_1") (pintype "passive"))
    )
    (net (code "78") (name "Net-(D259-A)") (class "Default")
      (node (ref "D259") (pin "1") (pinfunction "A_1") (pintype "passive"))
      (node (ref "S259") (pin "1") (pinfunction "1_1") (pintype "passive"))
    )
    (net (code "79") (name "Net-(D260-A)") (class "Default")
      (node (ref "D260") (pin "1") (pinfunction "A_1") (pintype "passive"))
      (node (ref "S260") (pin "1") (pinfunction "1_1") (pintype "passive"))
    )
    (net (code "80") (name "Net-(D261-A)") (class "Default")
      (node (ref "D261") (pin "1") (pinfunction "A_1") (pintype "passive"))
      (node (ref "S261") (pin "1") (pinfunction "1_1") (pintype "passive"))
      (node (ref "S261_1") (pin "1") (pinfunction "1_1") (pintype "passive"))
    )
    (net (code "81") (name "Net-(D262-A)") (class "Default")
      (node (ref "D262") (pin "1") (pinfunction "A_1") (pintype "passive"))
      (node (ref "S262") (pin "2") (pinfunction "2_2") (pintype "passive"))
    )
    (net (code "82") (name "Net-(D263-A)") (class "Default")
      (node (ref "D263") (pin "1") (pinfunction "A_1") (pintype "passive"))
      (node (ref "S263") (pin "2") (pinfunction "2_2") (pintype "passive"))
      (node (ref "S263_1") (pin "2") (pinfunction "2_2") (pintype "passive"))
    )
    (net (code "83") (name "Net-(D264-A)") (class "Default")
      (node (ref "D264") (pin "1") (pinfunction "A_1") (pintype "passive"))
      (node (ref "S264") (pin "1") (pinfunction "1_1") (pintype "passive"))
    )
    (net (code "84") (name "Net-(D265-A)") (class "Default")
      (node (ref "D265") (pin "1") (pinfunction "A_1") (pintype "passive"))
      (node (ref "S265") (pin "2") (pinfunction "2_2") (pintype "passive"))
    )
    (net (code "85") (name "Net-(D266-A)") (class "Default")
      (node (ref "D266") (pin "1") (pinfunction "A_1") (pintype "passive"))
      (node (ref "S266") (pin "1") (pinfunction "1_1") (pintype "passive"))
    )
    (net (code "86") (name "unconnected-(STAB1-Pad1)") (class "Default")
      (node (ref "STAB1") (pin "1") (pinfunction "1_1") (pintype "passive"))
    )
  )
)
